# BPSD.net
KiCad netlist of a schematic drawn in EAGLE
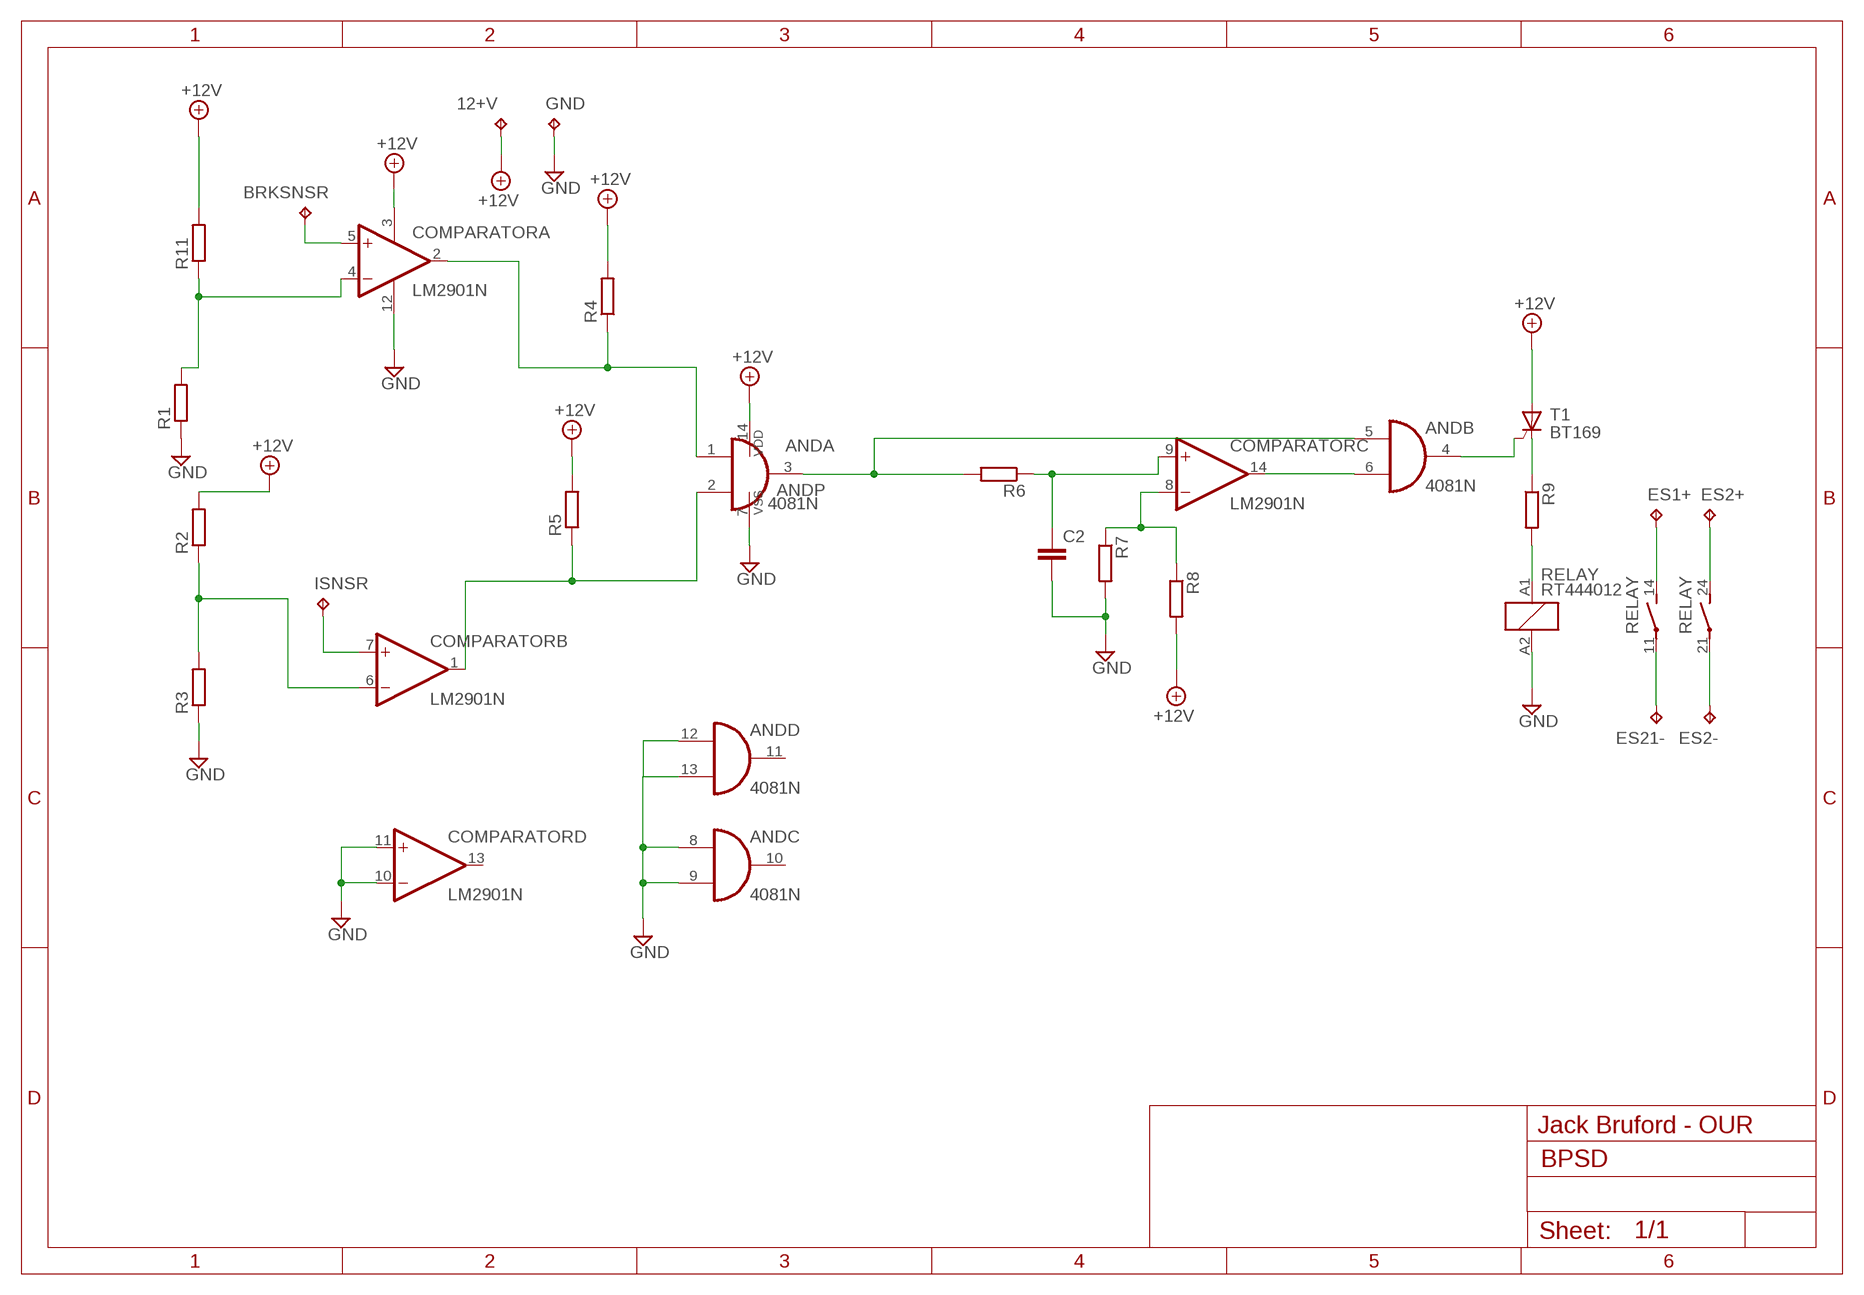
[diagram p0: schematic, sheet 1]

(export (version "E")
  (design (tool "Eeschema 10.0.6"))
  (components
    (comp (ref "12+V")
      (value "TPPAD1-13")
      (footprint "eagle-import:P1-13")
      (libsource (lib "eagle-import") (part "TPPAD1-13"))
    )
    (comp (ref "AND")
      (value "4081N")
      (footprint "eagle-import:DIL14")
      (libsource (lib "eagle-import") (part "4081N"))
    )
    (comp (ref "BRKSNSR")
      (value "TPPAD1-13")
      (footprint "eagle-import:P1-13")
      (libsource (lib "eagle-import") (part "TPPAD1-13"))
    )
    (comp (ref "C2")
      (value "C-EU050-024X044")
      (footprint "eagle-import:C050-024X044")
      (libsource (lib "eagle-import") (part "C-EU050-024X044"))
    )
    (comp (ref "COMPARATOR")
      (value "LM2901N")
      (footprint "eagle-import:DIL14")
      (libsource (lib "eagle-import") (part "LM2901N"))
    )
    (comp (ref "ES1+")
      (value "TPPAD1-13")
      (footprint "eagle-import:P1-13")
      (libsource (lib "eagle-import") (part "TPPAD1-13"))
    )
    (comp (ref "ES2+")
      (value "TPPAD1-13")
      (footprint "eagle-import:P1-13")
      (libsource (lib "eagle-import") (part "TPPAD1-13"))
    )
    (comp (ref "ES2-")
      (value "TPPAD1-13")
      (footprint "eagle-import:P1-13")
      (libsource (lib "eagle-import") (part "TPPAD1-13"))
    )
    (comp (ref "ES21-")
      (value "TPPAD1-13")
      (footprint "eagle-import:P1-13")
      (libsource (lib "eagle-import") (part "TPPAD1-13"))
    )
    (comp (ref "GND")
      (value "TPPAD1-13")
      (footprint "eagle-import:P1-13")
      (libsource (lib "eagle-import") (part "TPPAD1-13"))
    )
    (comp (ref "ISNSR")
      (value "TPPAD1-13")
      (footprint "eagle-import:P1-13")
      (libsource (lib "eagle-import") (part "TPPAD1-13"))
    )
    (comp (ref "R1")
      (value "R-EU_0207/15")
      (footprint "eagle-import:0207_15")
      (libsource (lib "eagle-import") (part "R-EU_0207/15"))
    )
    (comp (ref "R2")
      (value "R-EU_0207/15")
      (footprint "eagle-import:0207_15")
      (libsource (lib "eagle-import") (part "R-EU_0207/15"))
    )
    (comp (ref "R3")
      (value "R-EU_0207/15")
      (footprint "eagle-import:0207_15")
      (libsource (lib "eagle-import") (part "R-EU_0207/15"))
    )
    (comp (ref "R4")
      (value "R-EU_0207/15")
      (footprint "eagle-import:0207_15")
      (libsource (lib "eagle-import") (part "R-EU_0207/15"))
    )
    (comp (ref "R5")
      (value "R-EU_0207/15")
      (footprint "eagle-import:0207_15")
      (libsource (lib "eagle-import") (part "R-EU_0207/15"))
    )
    (comp (ref "R6")
      (value "R-EU_0207/15")
      (footprint "eagle-import:0207_15")
      (libsource (lib "eagle-import") (part "R-EU_0207/15"))
    )
    (comp (ref "R7")
      (value "R-EU_0207/15")
      (footprint "eagle-import:0207_15")
      (libsource (lib "eagle-import") (part "R-EU_0207/15"))
    )
    (comp (ref "R8")
      (value "R-EU_0207/15")
      (footprint "eagle-import:0207_15")
      (libsource (lib "eagle-import") (part "R-EU_0207/15"))
    )
    (comp (ref "R9")
      (value "R-EU_0207/15")
      (footprint "eagle-import:0207_15")
      (libsource (lib "eagle-import") (part "R-EU_0207/15"))
    )
    (comp (ref "R11")
      (value "R-EU_0207/15")
      (footprint "eagle-import:0207_15")
      (libsource (lib "eagle-import") (part "R-EU_0207/15"))
    )
    (comp (ref "RELAY")
      (value "RT444012")
      (footprint "eagle-import:RT2N_O")
      (libsource (lib "eagle-import") (part "RT44?4012"))
    )
    (comp (ref "T1")
      (value "BT169")
      (footprint "eagle-import:TO92-2")
      (libsource (lib "eagle-import") (part "BT169"))
    )
  )
  (nets
    (net (code "1") (name "+12V") (class "Default")
      (node (ref "12+V") (pin "TP") (pinfunction "TP_TP") (pintype "input"))
      (node (ref "AND") (pin "14") (pinfunction "VDD_14") (pintype "power_in"))
      (node (ref "COMPARATOR") (pin "3") (pinfunction "V+_3") (pintype "power_in"))
      (node (ref "R11") (pin "2") (pinfunction "2_2") (pintype "passive"))
      (node (ref "R2") (pin "2") (pinfunction "2_2") (pintype "passive"))
      (node (ref "R4") (pin "2") (pinfunction "2_2") (pintype "passive"))
      (node (ref "R5") (pin "2") (pinfunction "2_2") (pintype "passive"))
      (node (ref "R8") (pin "2") (pinfunction "2_2") (pintype "passive"))
      (node (ref "T1") (pin "A") (pinfunction "A_A") (pintype "passive"))
    )
    (net (code "2") (name "GND") (class "Default")
      (node (ref "AND") (pin "12") (pinfunction "I0_12") (pintype "input"))
      (node (ref "AND") (pin "13") (pinfunction "I1_13") (pintype "input"))
      (node (ref "AND") (pin "7") (pinfunction "VSS_7") (pintype "power_in"))
      (node (ref "AND") (pin "8") (pinfunction "I0_8") (pintype "input"))
      (node (ref "AND") (pin "9") (pinfunction "I1_9") (pintype "input"))
      (node (ref "C2") (pin "2") (pinfunction "2_2") (pintype "passive"))
      (node (ref "COMPARATOR") (pin "10") (pinfunction "-IN_10") (pintype "input"))
      (node (ref "COMPARATOR") (pin "11") (pinfunction "+IN_11") (pintype "input"))
      (node (ref "COMPARATOR") (pin "12") (pinfunction "V-_12") (pintype "power_in"))
      (node (ref "GND") (pin "TP") (pinfunction "TP_TP") (pintype "input"))
      (node (ref "R1") (pin "1") (pinfunction "1_1") (pintype "passive"))
      (node (ref "R3") (pin "1") (pinfunction "1_1") (pintype "passive"))
      (node (ref "R7") (pin "2") (pinfunction "2_2") (pintype "passive"))
      (node (ref "RELAY") (pin "A2") (pinfunction "2_A2") (pintype "passive"))
    )
    (net (code "3") (name "Net-(ANDA-I0)") (class "Default")
      (node (ref "AND") (pin "1") (pinfunction "I0_1") (pintype "input"))
      (node (ref "COMPARATOR") (pin "2") (pinfunction "OUT_2") (pintype "output"))
      (node (ref "R4") (pin "1") (pinfunction "1_1") (pintype "passive"))
    )
    (net (code "4") (name "Net-(ANDA-I1)") (class "Default")
      (node (ref "AND") (pin "2") (pinfunction "I1_2") (pintype "input"))
      (node (ref "COMPARATOR") (pin "1") (pinfunction "OUT_1") (pintype "output"))
      (node (ref "R5") (pin "1") (pinfunction "1_1") (pintype "passive"))
    )
    (net (code "5") (name "Net-(ANDA-O)") (class "Default")
      (node (ref "AND") (pin "3") (pinfunction "O_3") (pintype "output"))
      (node (ref "AND") (pin "5") (pinfunction "I0_5") (pintype "input"))
      (node (ref "R6") (pin "2") (pinfunction "2_2") (pintype "passive"))
    )
    (net (code "6") (name "Net-(ANDB-I1)") (class "Default")
      (node (ref "AND") (pin "6") (pinfunction "I1_6") (pintype "input"))
      (node (ref "COMPARATOR") (pin "14") (pinfunction "OUT_14") (pintype "output"))
    )
    (net (code "7") (name "Net-(ANDB-O)") (class "Default")
      (node (ref "AND") (pin "4") (pinfunction "O_4") (pintype "output"))
      (node (ref "T1") (pin "G") (pinfunction "G_G") (pintype "passive"))
    )
    (net (code "8") (name "Net-(COMPARATORA-+IN)") (class "Default")
      (node (ref "BRKSNSR") (pin "TP") (pinfunction "TP_TP") (pintype "input"))
      (node (ref "COMPARATOR") (pin "5") (pinfunction "+IN_5") (pintype "input"))
    )
    (net (code "9") (name "Net-(COMPARATORA--IN)") (class "Default")
      (node (ref "COMPARATOR") (pin "4") (pinfunction "-IN_4") (pintype "input"))
      (node (ref "R1") (pin "2") (pinfunction "2_2") (pintype "passive"))
      (node (ref "R11") (pin "1") (pinfunction "1_1") (pintype "passive"))
    )
    (net (code "10") (name "Net-(COMPARATORB-+IN)") (class "Default")
      (node (ref "COMPARATOR") (pin "7") (pinfunction "+IN_7") (pintype "input"))
      (node (ref "ISNSR") (pin "TP") (pinfunction "TP_TP") (pintype "input"))
    )
    (net (code "11") (name "Net-(COMPARATORB--IN)") (class "Default")
      (node (ref "COMPARATOR") (pin "6") (pinfunction "-IN_6") (pintype "input"))
      (node (ref "R2") (pin "1") (pinfunction "1_1") (pintype "passive"))
      (node (ref "R3") (pin "2") (pinfunction "2_2") (pintype "passive"))
    )
    (net (code "12") (name "Net-(COMPARATORC-+IN)") (class "Default")
      (node (ref "C2") (pin "1") (pinfunction "1_1") (pintype "passive"))
      (node (ref "COMPARATOR") (pin "9") (pinfunction "+IN_9") (pintype "input"))
      (node (ref "R6") (pin "1") (pinfunction "1_1") (pintype "passive"))
    )
    (net (code "13") (name "Net-(COMPARATORC--IN)") (class "Default")
      (node (ref "COMPARATOR") (pin "8") (pinfunction "-IN_8") (pintype "input"))
      (node (ref "R7") (pin "1") (pinfunction "1_1") (pintype "passive"))
      (node (ref "R8") (pin "1") (pinfunction "1_1") (pintype "passive"))
    )
    (net (code "14") (name "Net-(R9-Pad1)") (class "Default")
      (node (ref "R9") (pin "1") (pinfunction "1_1") (pintype "passive"))
      (node (ref "T1") (pin "C") (pinfunction "C_C") (pintype "passive"))
    )
    (net (code "15") (name "Net-(RELAYA-1)") (class "Default")
      (node (ref "R9") (pin "2") (pinfunction "2_2") (pintype "passive"))
      (node (ref "RELAY") (pin "A1") (pinfunction "1_A1") (pintype "passive"))
    )
    (net (code "16") (name "Net-(RELAYB-P)") (class "Default")
      (node (ref "ES21-") (pin "TP") (pinfunction "TP_TP") (pintype "input"))
      (node (ref "RELAY") (pin "11") (pinfunction "P_11") (pintype "passive"))
    )
    (net (code "17") (name "Net-(RELAYB-S)") (class "Default")
      (node (ref "ES1+") (pin "TP") (pinfunction "TP_TP") (pintype "input"))
      (node (ref "RELAY") (pin "14") (pinfunction "S_14") (pintype "passive"))
    )
    (net (code "18") (name "Net-(RELAYC-P)") (class "Default")
      (node (ref "ES2-") (pin "TP") (pinfunction "TP_TP") (pintype "input"))
      (node (ref "RELAY") (pin "21") (pinfunction "P_21") (pintype "passive"))
    )
    (net (code "19") (name "Net-(RELAYC-S)") (class "Default")
      (node (ref "ES2+") (pin "TP") (pinfunction "TP_TP") (pintype "input"))
      (node (ref "RELAY") (pin "24") (pinfunction "S_24") (pintype "passive"))
    )
    (net (code "20") (name "unconnected-(ANDC-O-Pad10)") (class "Default")
      (node (ref "AND") (pin "10") (pinfunction "O_10") (pintype "output"))
    )
    (net (code "21") (name "unconnected-(ANDD-O-Pad11)") (class "Default")
      (node (ref "AND") (pin "11") (pinfunction "O_11") (pintype "output"))
    )
    (net (code "22") (name "unconnected-(COMPARATORD-OUT-Pad13)") (class "Default")
      (node (ref "COMPARATOR") (pin "13") (pinfunction "OUT_13") (pintype "output"))
    )
  )
)
